# kill_switch.net
KiCad netlist of a schematic drawn in Altium Designer
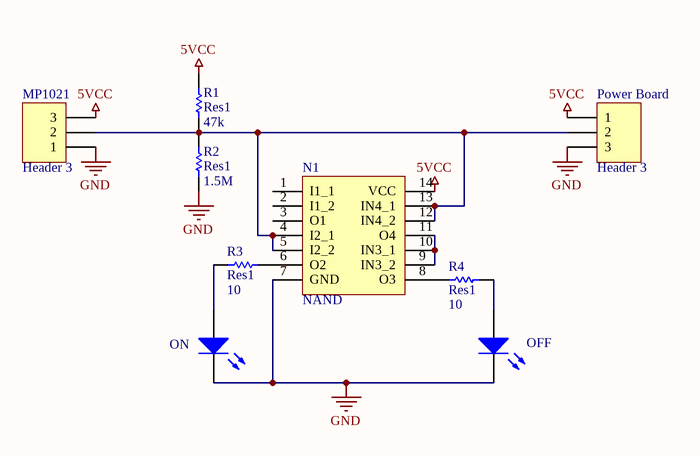
[diagram p0: kill_switch.SchDoc]

(export (version "E")
  (design (tool "Eeschema 10.0.6"))
  (components
    (comp (ref "MP1021")
      (value "Header 3")
      (footprint "HDR1X3")
      (description "Header, 3-Pin")
      (fields (field (name "PUBLISHER") "Altium Limited"))
      (libsource (lib "") (part "Header 3_1"))
    )
    (comp (ref "N1") (value "NAND") (description "MM74HC00M") (libsource (lib "sonar") (part "NAND")))
    (comp (ref "OFF")
      (value "LED2")
      (footprint "3.2X1.6X1.1")
      (description "White CRE LED, max current 1A")
      (fields (field (name "PUBLISHER") "Altium Limited"))
      (libsource (lib "Miscellaneous Devices") (part "LED2"))
    )
    (comp (ref "ON")
      (value "~")
      (footprint "3.2X1.6X1.1")
      (description "Green CRE LED, max current .7A")
      (fields (field (name "PUBLISHER") "Altium Limited"))
      (libsource (lib "Miscellaneous Devices") (part "LED2"))
    )
    (comp (ref "Power Board")
      (value "Header 3")
      (footprint "HDR1X3")
      (description "Header, 3-Pin")
      (fields (field (name "PUBLISHER") "Altium Limited"))
      (libsource (lib "Miscellaneous Connectors") (part "Header 3"))
    )
    (comp (ref "R1")
      (value "Res1")
      (footprint "AXIAL-0.3")
      (description "Resistor")
      (fields (field (name "ALTIUM_VALUE") "47k") (field (name "PUBLISHER") "Altium Limited"))
      (libsource (lib "Miscellaneous Devices") (part "Res1"))
    )
    (comp (ref "R2")
      (value "Res1")
      (footprint "AXIAL-0.3")
      (description "Resistor")
      (fields (field (name "ALTIUM_VALUE") "1.5M") (field (name "PUBLISHER") "Altium Limited"))
      (libsource (lib "Miscellaneous Devices") (part "Res1"))
    )
    (comp (ref "R3")
      (value "Res1")
      (footprint "AXIAL-0.3")
      (description "Resistor")
      (fields (field (name "ALTIUM_VALUE") "10") (field (name "PUBLISHER") "Altium Limited"))
      (libsource (lib "Miscellaneous Devices") (part "Res1"))
    )
    (comp (ref "R4")
      (value "Res1")
      (footprint "AXIAL-0.3")
      (description "Resistor")
      (fields (field (name "ALTIUM_VALUE") "10") (field (name "PUBLISHER") "Altium Limited"))
      (libsource (lib "Miscellaneous Devices") (part "Res1"))
    )
  )
  (nets
    (net (code "1") (name "5VCC") (class "Default")
      (node (ref "MP1021") (pin "3") (pinfunction "3_3") (pintype "passive"))
      (node (ref "N1") (pin "14") (pinfunction "VCC_14") (pintype "power_in"))
      (node (ref "Power Board") (pin "1") (pinfunction "1_1") (pintype "passive"))
      (node (ref "R1") (pin "2") (pinfunction "2_2") (pintype "passive"))
    )
    (net (code "2") (name "GND") (class "Default")
      (node (ref "MP1021") (pin "1") (pinfunction "1_1") (pintype "passive"))
      (node (ref "N1") (pin "7") (pinfunction "GND_7") (pintype "power_in"))
      (node (ref "OFF") (pin "2") (pinfunction "K_2") (pintype "passive"))
      (node (ref "ON") (pin "2") (pinfunction "K_2") (pintype "passive"))
      (node (ref "Power Board") (pin "3") (pinfunction "3_3") (pintype "passive"))
      (node (ref "R2") (pin "1") (pinfunction "1_1") (pintype "passive"))
    )
    (net (code "3") (name "Net-(N1-I2_1)") (class "Default")
      (node (ref "MP1021") (pin "2") (pinfunction "2_2") (pintype "passive"))
      (node (ref "N1") (pin "12") (pinfunction "IN4_2_12") (pintype "power_in"))
      (node (ref "N1") (pin "13") (pinfunction "IN4_1_13") (pintype "power_in"))
      (node (ref "N1") (pin "4") (pinfunction "I2_1_4") (pintype "power_in"))
      (node (ref "N1") (pin "5") (pinfunction "I2_2_5") (pintype "power_in"))
      (node (ref "Power Board") (pin "2") (pinfunction "2_2") (pintype "passive"))
      (node (ref "R1") (pin "1") (pinfunction "1_1") (pintype "passive"))
      (node (ref "R2") (pin "2") (pinfunction "2_2") (pintype "passive"))
    )
    (net (code "4") (name "Net-(N1-IN3_1)") (class "Default")
      (node (ref "N1") (pin "10") (pinfunction "IN3_1_10") (pintype "power_in"))
      (node (ref "N1") (pin "11") (pinfunction "O4_11") (pintype "power_in"))
      (node (ref "N1") (pin "9") (pinfunction "IN3_2_9") (pintype "power_in"))
    )
    (net (code "5") (name "Net-(N1-O2)") (class "Default")
      (node (ref "N1") (pin "6") (pinfunction "O2_6") (pintype "power_in"))
      (node (ref "R3") (pin "1") (pinfunction "1_1") (pintype "passive"))
    )
    (net (code "6") (name "Net-(N1-O3)") (class "Default")
      (node (ref "N1") (pin "8") (pinfunction "O3_8") (pintype "power_in"))
      (node (ref "R4") (pin "2") (pinfunction "2_2") (pintype "passive"))
    )
    (net (code "7") (name "Net-(OFF-A)") (class "Default")
      (node (ref "OFF") (pin "1") (pinfunction "A_1") (pintype "passive"))
      (node (ref "R4") (pin "1") (pinfunction "1_1") (pintype "passive"))
    )
    (net (code "8") (name "Net-(ON-A)") (class "Default")
      (node (ref "ON") (pin "1") (pinfunction "A_1") (pintype "passive"))
      (node (ref "R3") (pin "2") (pinfunction "2_2") (pintype "passive"))
    )
    (net (code "9") (name "unconnected-(N1-I1_1-Pad1)") (class "Default")
      (node (ref "N1") (pin "1") (pinfunction "I1_1_1") (pintype "power_in"))
    )
    (net (code "10") (name "unconnected-(N1-I1_2-Pad2)") (class "Default")
      (node (ref "N1") (pin "2") (pinfunction "I1_2_2") (pintype "power_in"))
    )
    (net (code "11") (name "unconnected-(N1-O1-Pad3)") (class "Default")
      (node (ref "N1") (pin "3") (pinfunction "O1_3") (pintype "power_in"))
    )
  )
)
